# Sensor_Board.net
KiCad netlist of a schematic drawn in EAGLE
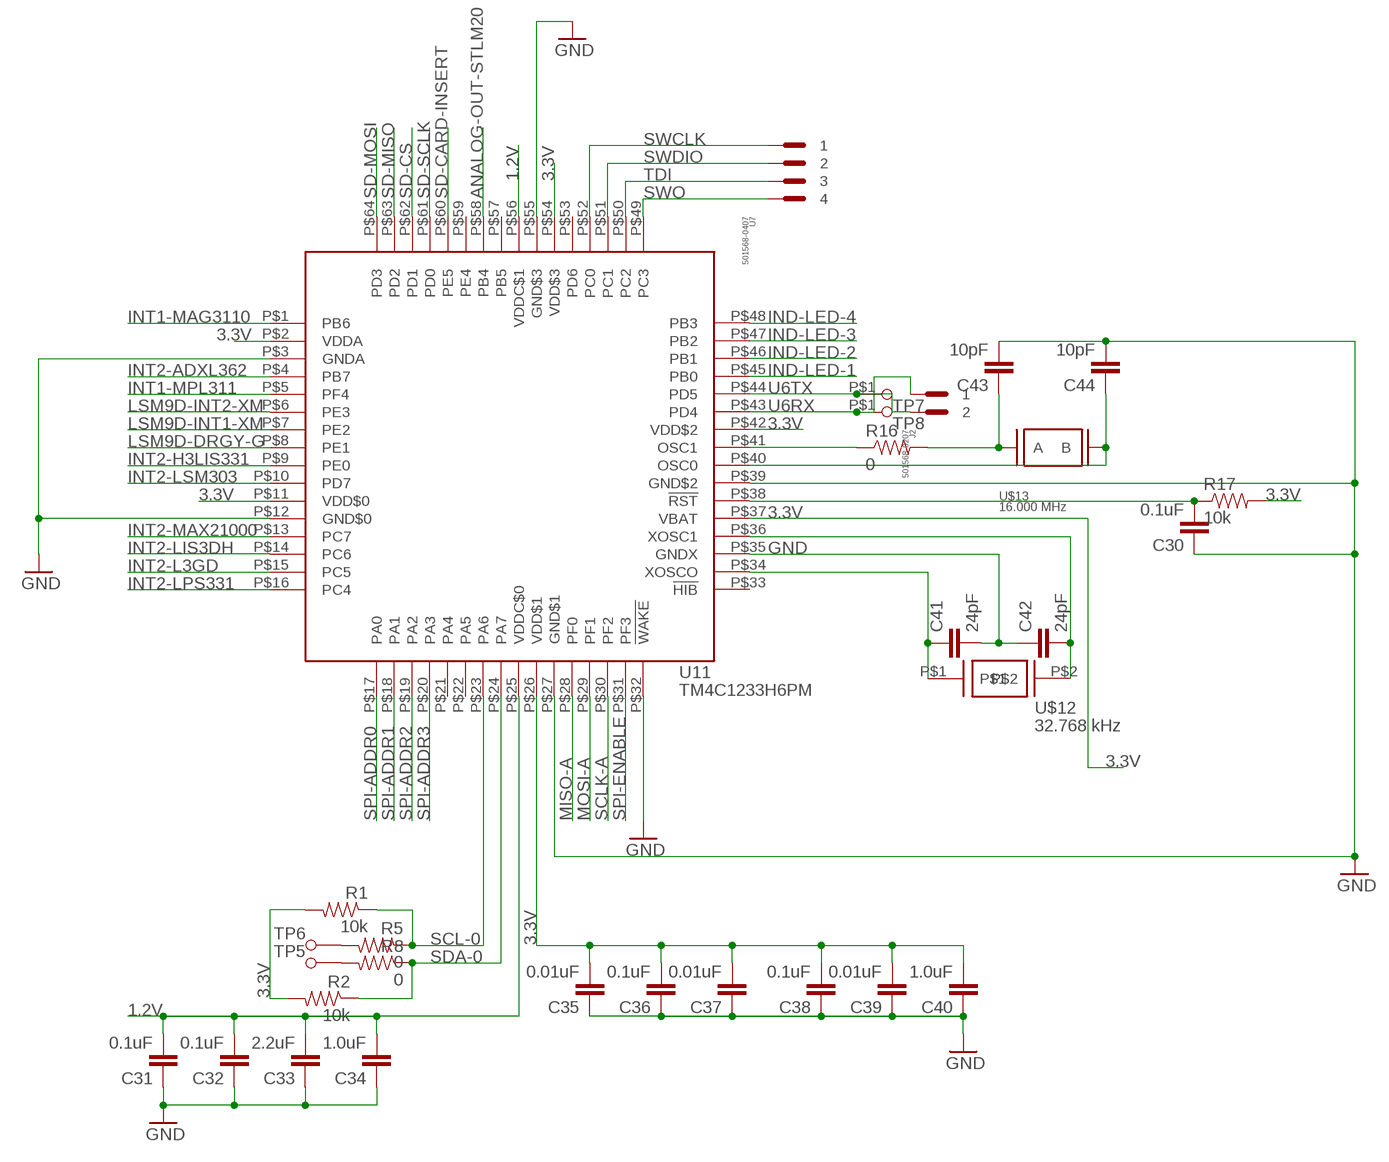
[diagram p0: schematic, sheet 1]
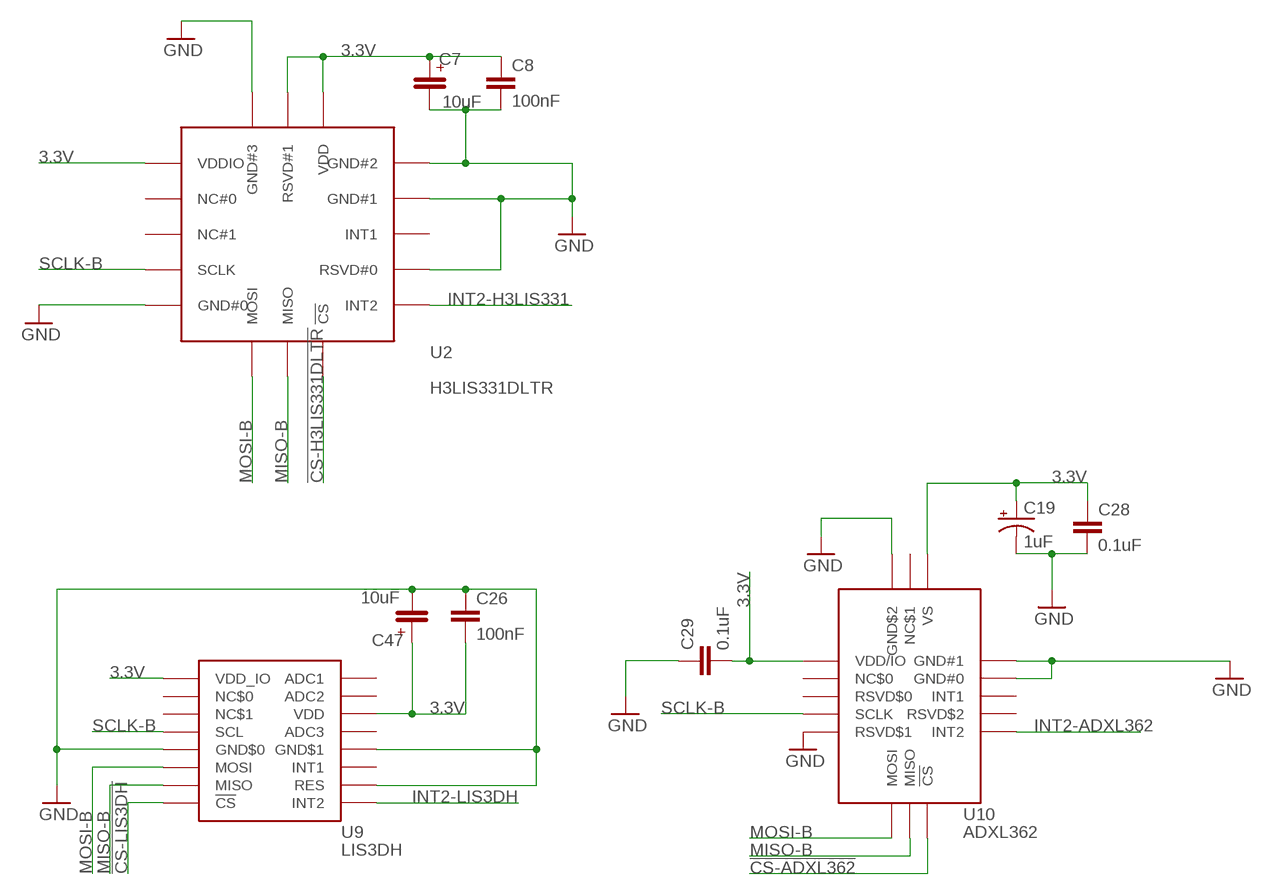
[diagram p1: schematic, sheet 2]
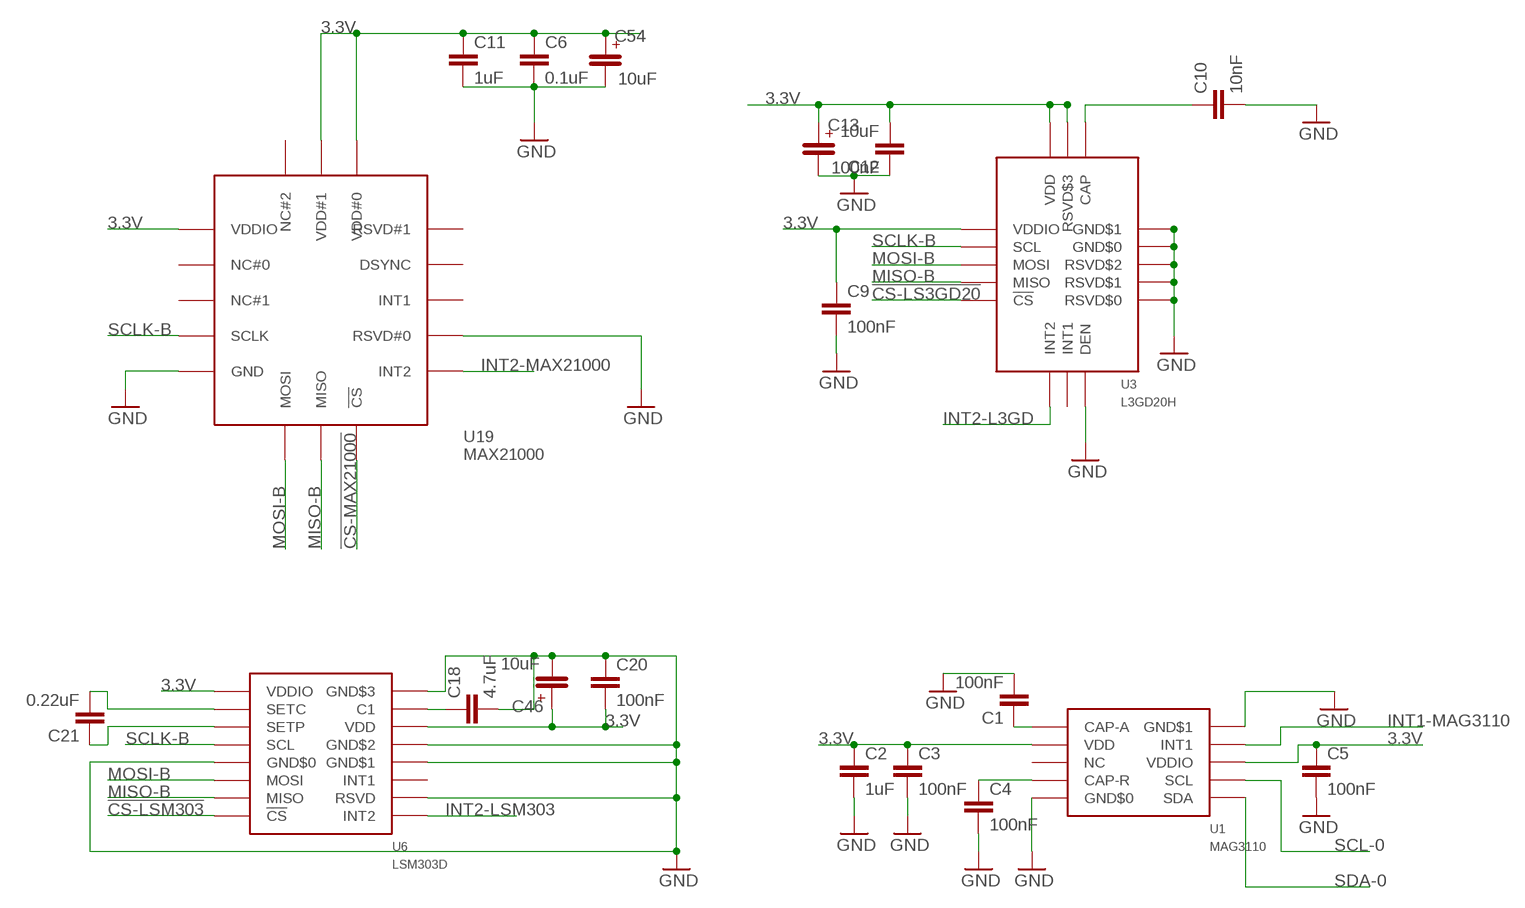
[diagram p2: schematic, sheet 3]
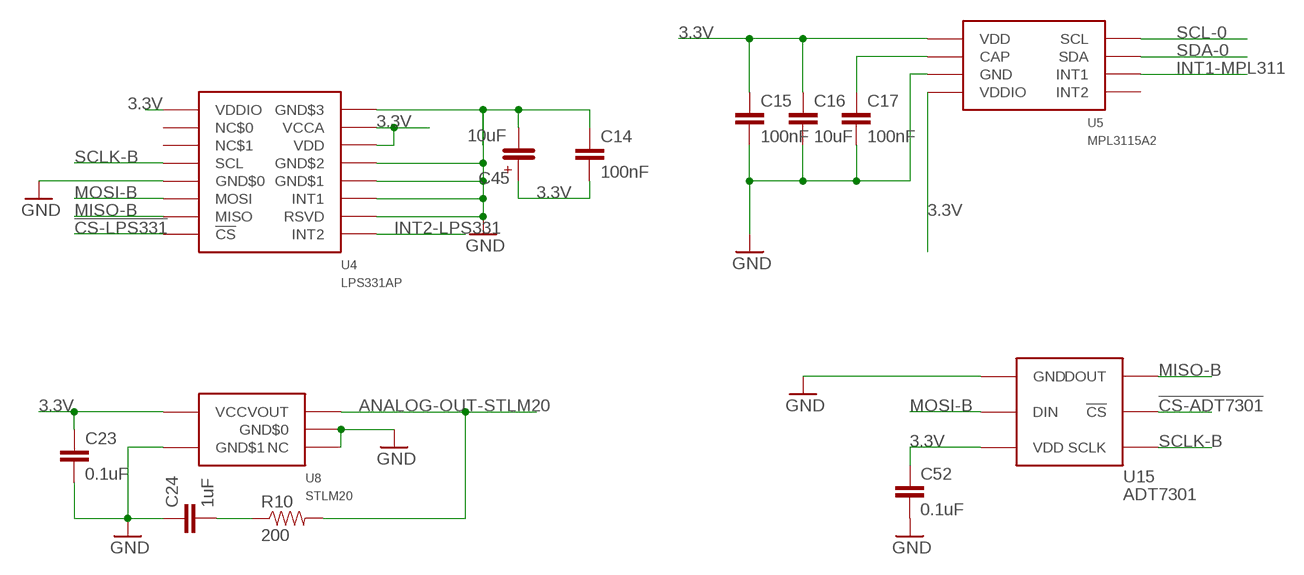
[diagram p3: schematic, sheet 4]
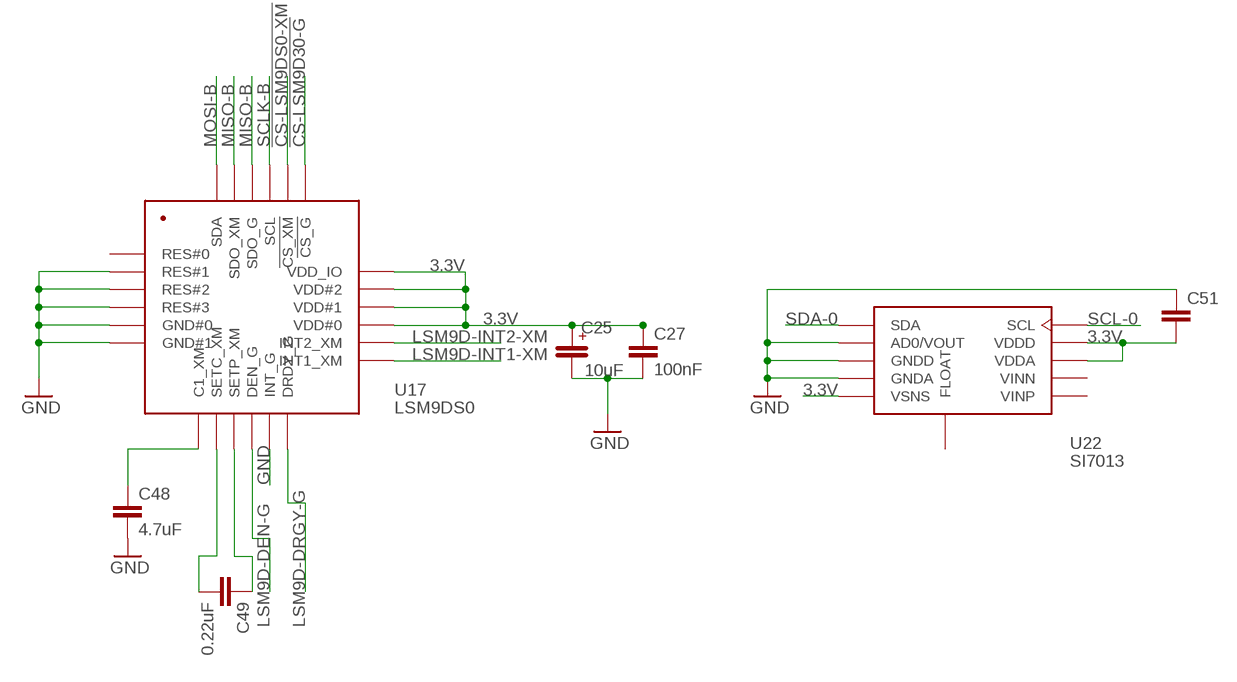
[diagram p4: schematic, sheet 5]
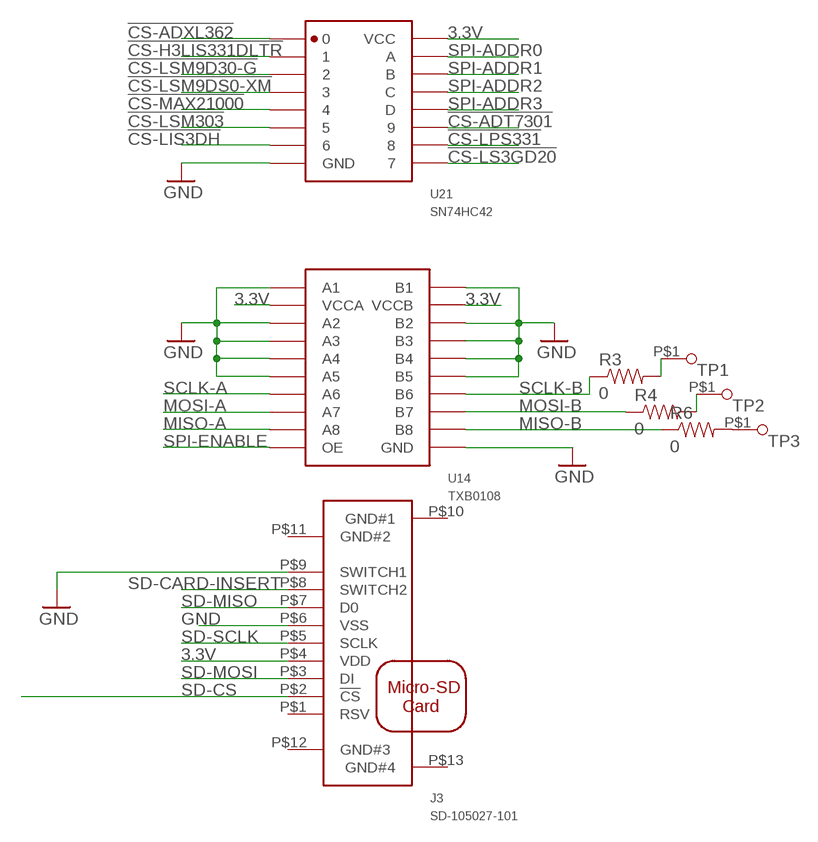
[diagram p5: schematic, sheet 6]
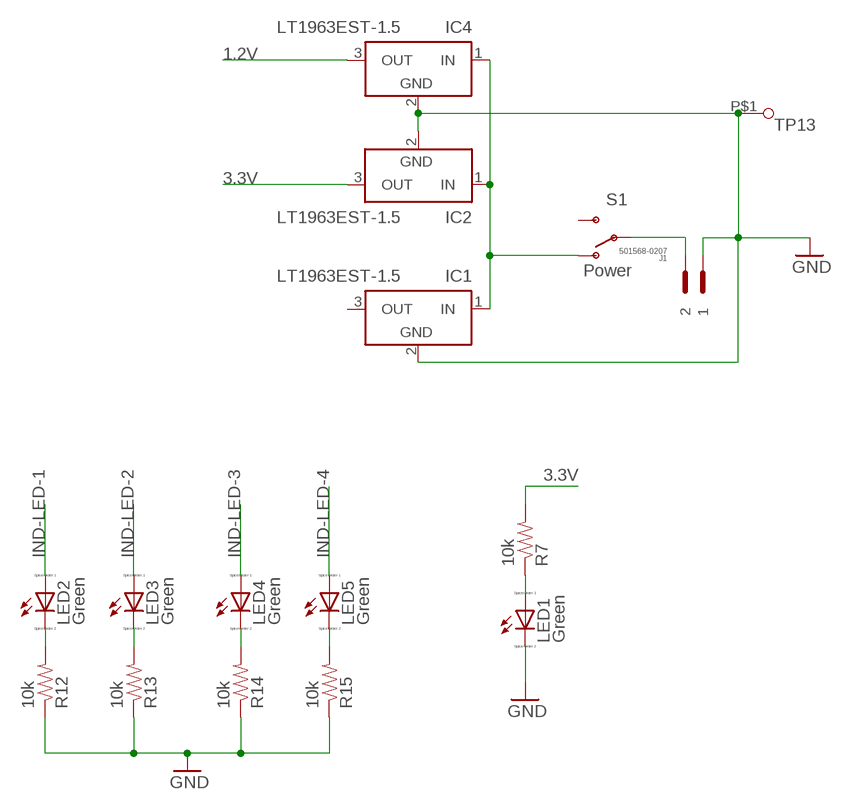
[diagram p6: schematic, sheet 7]

(export (version "E")
  (design (tool "Eeschema 10.0.6"))
  (components
    (comp (ref "C25")
      (value "10uF")
      (footprint "eagle-import:4.3X7.3SMD")
      (libsource (lib "eagle-import") (part "EEFCD0J100ER"))
    )
    (comp (ref "C27")
      (value "100nF")
      (footprint "eagle-import:C0402")
      (libsource (lib "eagle-import") (part "CAPACITOR0402"))
    )
    (comp (ref "C48")
      (value "4.7uF")
      (footprint "eagle-import:C0402")
      (libsource (lib "eagle-import") (part "CAPACITOR0402"))
    )
    (comp (ref "C49")
      (value "0.22uF")
      (footprint "eagle-import:C0402")
      (libsource (lib "eagle-import") (part "CAPACITOR0402"))
    )
    (comp (ref "C51")
      (value "CAPACITOR0402")
      (footprint "eagle-import:C0402")
      (libsource (lib "eagle-import") (part "CAPACITOR0402"))
    )
    (comp (ref "U17")
      (value "LSM9DS0")
      (footprint "eagle-import:LGA-24(4X4)")
      (libsource (lib "eagle-import") (part "LSM9DS0"))
    )
    (comp (ref "U22")
      (value "SI7013")
      (footprint "eagle-import:DFN-10(3X3)")
      (libsource (lib "eagle-import") (part "SI7013"))
    )
    (comp (ref "IC1")
      (value "LT1963EST-1.5")
      (footprint "eagle-import:SOT223")
      (libsource (lib "eagle-import") (part "LT1963EST-1.5"))
    )
    (comp (ref "IC2")
      (value "LT1963EST-1.5")
      (footprint "eagle-import:SOT223")
      (libsource (lib "eagle-import") (part "LT1963EST-1.5"))
    )
    (comp (ref "IC4")
      (value "LT1963EST-1.5")
      (footprint "eagle-import:SOT223")
      (libsource (lib "eagle-import") (part "LT1963EST-1.5"))
    )
    (comp (ref "J1")
      (value "501568-0207")
      (footprint "eagle-import:501568-0207")
      (libsource (lib "eagle-import") (part "501568-0207"))
    )
    (comp (ref "LED1")
      (value "Green")
      (footprint "eagle-import:LED_SML0603")
      (libsource (lib "eagle-import") (part "LED_ESML0603"))
    )
    (comp (ref "LED2")
      (value "Green")
      (footprint "eagle-import:LED_SML0603")
      (libsource (lib "eagle-import") (part "LED_ESML0603"))
    )
    (comp (ref "LED3")
      (value "Green")
      (footprint "eagle-import:LED_SML0603")
      (libsource (lib "eagle-import") (part "LED_ESML0603"))
    )
    (comp (ref "LED4")
      (value "Green")
      (footprint "eagle-import:LED_SML0603")
      (libsource (lib "eagle-import") (part "LED_ESML0603"))
    )
    (comp (ref "LED5")
      (value "Green")
      (footprint "eagle-import:LED_SML0603")
      (libsource (lib "eagle-import") (part "LED_ESML0603"))
    )
    (comp (ref "R7")
      (value "10k")
      (footprint "eagle-import:R0402")
      (libsource (lib "eagle-import") (part "RESISTOR"))
    )
    (comp (ref "R12")
      (value "10k")
      (footprint "eagle-import:R0402")
      (libsource (lib "eagle-import") (part "RESISTOR"))
    )
    (comp (ref "R13")
      (value "10k")
      (footprint "eagle-import:R0402")
      (libsource (lib "eagle-import") (part "RESISTOR"))
    )
    (comp (ref "R14")
      (value "10k")
      (footprint "eagle-import:R0402")
      (libsource (lib "eagle-import") (part "RESISTOR"))
    )
    (comp (ref "R15")
      (value "10k")
      (footprint "eagle-import:R0402")
      (libsource (lib "eagle-import") (part "RESISTOR"))
    )
    (comp (ref "S1")
      (value "Power")
      (footprint "eagle-import:SWITCH-SPST-SMD-A")
      (libsource (lib "eagle-import") (part "SWITCH-SPDT-SMD-A"))
    )
    (comp (ref "TP13")
      (value "TESTPAD(ROUND)")
      (footprint "eagle-import:TESTPAD(ROUND)")
      (libsource (lib "eagle-import") (part "Kas-Passives_TESTPAD(ROUND)"))
    )
    (comp (ref "C30")
      (value "0.1uF")
      (footprint "eagle-import:C0402")
      (libsource (lib "eagle-import") (part "CAPACITOR0402"))
    )
    (comp (ref "C31")
      (value "0.1uF")
      (footprint "eagle-import:C0402")
      (libsource (lib "eagle-import") (part "CAPACITOR0402"))
    )
    (comp (ref "C32")
      (value "0.1uF")
      (footprint "eagle-import:C0402")
      (libsource (lib "eagle-import") (part "CAPACITOR0402"))
    )
    (comp (ref "C33")
      (value "2.2uF")
      (footprint "eagle-import:C0402")
      (libsource (lib "eagle-import") (part "CAPACITOR0402"))
    )
    (comp (ref "C34")
      (value "1.0uF")
      (footprint "eagle-import:C0402")
      (libsource (lib "eagle-import") (part "CAPACITOR0402"))
    )
    (comp (ref "C35")
      (value "0.01uF")
      (footprint "eagle-import:C0402")
      (libsource (lib "eagle-import") (part "CAPACITOR0402"))
    )
    (comp (ref "C36")
      (value "0.1uF")
      (footprint "eagle-import:C0402")
      (libsource (lib "eagle-import") (part "CAPACITOR0402"))
    )
    (comp (ref "C37")
      (value "0.01uF")
      (footprint "eagle-import:C0402")
      (libsource (lib "eagle-import") (part "CAPACITOR0402"))
    )
    (comp (ref "C38")
      (value "0.1uF")
      (footprint "eagle-import:C0402")
      (libsource (lib "eagle-import") (part "CAPACITOR0402"))
    )
    (comp (ref "C39")
      (value "0.01uF")
      (footprint "eagle-import:C0402")
      (libsource (lib "eagle-import") (part "CAPACITOR0402"))
    )
    (comp (ref "C40")
      (value "1.0uF")
      (footprint "eagle-import:C0402")
      (libsource (lib "eagle-import") (part "CAPACITOR0402"))
    )
    (comp (ref "C41")
      (value "24pF")
      (footprint "eagle-import:C0402")
      (libsource (lib "eagle-import") (part "CAPACITOR0402"))
    )
    (comp (ref "C42")
      (value "24pF")
      (footprint "eagle-import:C0402")
      (libsource (lib "eagle-import") (part "CAPACITOR0402"))
    )
    (comp (ref "C43")
      (value "10pF")
      (footprint "eagle-import:C0402")
      (libsource (lib "eagle-import") (part "CAPACITOR0402"))
    )
    (comp (ref "C44")
      (value "10pF")
      (footprint "eagle-import:C0402")
      (libsource (lib "eagle-import") (part "CAPACITOR0402"))
    )
    (comp (ref "J2")
      (value "501568-0207")
      (footprint "eagle-import:501568-0207")
      (libsource (lib "eagle-import") (part "501568-0207"))
    )
    (comp (ref "R1")
      (value "10k")
      (footprint "eagle-import:R0402")
      (libsource (lib "eagle-import") (part "RESISTOR"))
    )
    (comp (ref "R2")
      (value "10k")
      (footprint "eagle-import:R0402")
      (libsource (lib "eagle-import") (part "RESISTOR"))
    )
    (comp (ref "R5")
      (value "0")
      (footprint "eagle-import:R0402")
      (libsource (lib "eagle-import") (part "RESISTOR"))
    )
    (comp (ref "R8")
      (value "0")
      (footprint "eagle-import:R0402")
      (libsource (lib "eagle-import") (part "RESISTOR"))
    )
    (comp (ref "R16")
      (value "0")
      (footprint "eagle-import:R0402")
      (libsource (lib "eagle-import") (part "RESISTOR"))
    )
    (comp (ref "R17")
      (value "10k")
      (footprint "eagle-import:R0402")
      (libsource (lib "eagle-import") (part "RESISTOR"))
    )
    (comp (ref "TP5")
      (value "TESTPAD(ROUND)")
      (footprint "eagle-import:TESTPAD(ROUND)")
      (libsource (lib "eagle-import") (part "TESTPAD(ROUND)"))
    )
    (comp (ref "TP6")
      (value "TESTPAD(ROUND)")
      (footprint "eagle-import:TESTPAD(ROUND)")
      (libsource (lib "eagle-import") (part "TESTPAD(ROUND)"))
    )
    (comp (ref "TP7")
      (value "TESTPAD(ROUND)")
      (footprint "eagle-import:TESTPAD(ROUND)")
      (libsource (lib "eagle-import") (part "Kas-Passives_TESTPAD(ROUND)"))
    )
    (comp (ref "TP8")
      (value "TESTPAD(ROUND)")
      (footprint "eagle-import:TESTPAD(ROUND)")
      (libsource (lib "eagle-import") (part "Kas-Passives_TESTPAD(ROUND)"))
    )
    (comp (ref "U$12")
      (value "32.768 kHz")
      (footprint "eagle-import:2-SMD(3.2X1.5)")
      (libsource (lib "eagle-import") (part "ABS07L"))
    )
    (comp (ref "U$13")
      (value "16.000 MHz")
      (footprint "eagle-import:4-SMD(3.2X2.5)")
      (libsource (lib "eagle-import") (part "NX3225GA"))
    )
    (comp (ref "U7")
      (value "501568-0407")
      (footprint "eagle-import:501568-0407")
      (libsource (lib "eagle-import") (part "501568-0407"))
    )
    (comp (ref "U11")
      (value "TM4C1233H6PM")
      (footprint "eagle-import:S-PQFP-G64")
      (libsource (lib "eagle-import") (part "TM4C1233H6PM"))
    )
    (comp (ref "C1")
      (value "100nF")
      (footprint "eagle-import:C0402")
      (libsource (lib "eagle-import") (part "CAPACITOR0402"))
    )
    (comp (ref "C2")
      (value "1uF")
      (footprint "eagle-import:C0402")
      (libsource (lib "eagle-import") (part "CAPACITOR0402"))
    )
    (comp (ref "C3")
      (value "100nF")
      (footprint "eagle-import:C0402")
      (libsource (lib "eagle-import") (part "CAPACITOR0402"))
    )
    (comp (ref "C4")
      (value "100nF")
      (footprint "eagle-import:C0402")
      (libsource (lib "eagle-import") (part "CAPACITOR0402"))
    )
    (comp (ref "C5")
      (value "100nF")
      (footprint "eagle-import:C0402")
      (libsource (lib "eagle-import") (part "CAPACITOR0402"))
    )
    (comp (ref "C6")
      (value "0.1uF")
      (footprint "eagle-import:C0402")
      (libsource (lib "eagle-import") (part "CAPACITOR0402"))
    )
    (comp (ref "C9")
      (value "100nF")
      (footprint "eagle-import:C0402")
      (libsource (lib "eagle-import") (part "CAPACITOR0402"))
    )
    (comp (ref "C10")
      (value "10nF")
      (footprint "eagle-import:C0402")
      (libsource (lib "eagle-import") (part "CAPACITOR0402"))
    )
    (comp (ref "C11")
      (value "1uF")
      (footprint "eagle-import:C0402")
      (libsource (lib "eagle-import") (part "CAPACITOR0402"))
    )
    (comp (ref "C12")
      (value "10uF")
      (footprint "eagle-import:C0402")
      (libsource (lib "eagle-import") (part "CAPACITOR0402"))
    )
    (comp (ref "C13")
      (value "100nF")
      (footprint "eagle-import:4.3X7.3SMD")
      (libsource (lib "eagle-import") (part "EEFCD0J100ER"))
    )
    (comp (ref "C18")
      (value "4.7uF")
      (footprint "eagle-import:C0402")
      (libsource (lib "eagle-import") (part "CAPACITOR0402"))
    )
    (comp (ref "C20")
      (value "100nF")
      (footprint "eagle-import:C0402")
      (libsource (lib "eagle-import") (part "CAPACITOR0402"))
    )
    (comp (ref "C21")
      (value "0.22uF")
      (footprint "eagle-import:C0402")
      (libsource (lib "eagle-import") (part "CAPACITOR0402"))
    )
    (comp (ref "C46")
      (value "10uF")
      (footprint "eagle-import:4.3X7.3SMD")
      (libsource (lib "eagle-import") (part "EEFCD0J100ER"))
    )
    (comp (ref "C54")
      (value "10uF")
      (footprint "eagle-import:4.3X7.3SMD")
      (libsource (lib "eagle-import") (part "EEFCD0J100ER"))
    )
    (comp (ref "U1")
      (value "MAG3110")
      (footprint "eagle-import:DFN-10(2X2)")
      (libsource (lib "eagle-import") (part "MAG3110"))
    )
    (comp (ref "U3")
      (value "L3GD20H")
      (footprint "eagle-import:LGA-16(3X3)")
      (libsource (lib "eagle-import") (part "L3GD20H"))
    )
    (comp (ref "U6")
      (value "LSM303D")
      (footprint "eagle-import:LGA-16(3X3)")
      (libsource (lib "eagle-import") (part "LSM303D"))
    )
    (comp (ref "U19")
      (value "MAX21000")
      (footprint "eagle-import:LGA-16(3X3)")
      (libsource (lib "eagle-import") (part "MAX21000"))
    )
    (comp (ref "J3")
      (value "SD-105027-101")
      (footprint "eagle-import:SD-105027-1001")
      (libsource (lib "eagle-import") (part "SD-105027-101"))
    )
    (comp (ref "R3")
      (value "0")
      (footprint "eagle-import:R0402")
      (libsource (lib "eagle-import") (part "RESISTOR"))
    )
    (comp (ref "R4")
      (value "0")
      (footprint "eagle-import:R0402")
      (libsource (lib "eagle-import") (part "RESISTOR"))
    )
    (comp (ref "R6")
      (value "0")
      (footprint "eagle-import:R0402")
      (libsource (lib "eagle-import") (part "RESISTOR"))
    )
    (comp (ref "TP1")
      (value "TESTPAD(ROUND)")
      (footprint "eagle-import:TESTPAD(ROUND)")
      (libsource (lib "eagle-import") (part "Kas-Passives_TESTPAD(ROUND)"))
    )
    (comp (ref "TP2")
      (value "TESTPAD(ROUND)")
      (footprint "eagle-import:TESTPAD(ROUND)")
      (libsource (lib "eagle-import") (part "Kas-Passives_TESTPAD(ROUND)"))
    )
    (comp (ref "TP3")
      (value "TESTPAD(ROUND)")
      (footprint "eagle-import:TESTPAD(ROUND)")
      (libsource (lib "eagle-import") (part "Kas-Passives_TESTPAD(ROUND)"))
    )
    (comp (ref "U14")
      (value "TXB0108")
      (footprint "eagle-import:TSSOP-(PW)-20")
      (libsource (lib "eagle-import") (part "TXB0108"))
    )
    (comp (ref "U21")
      (value "SN74HC42")
      (footprint "eagle-import:SOIC-16")
      (libsource (lib "eagle-import") (part "SN74HC42"))
    )
    (comp (ref "C14")
      (value "100nF")
      (footprint "eagle-import:C0402")
      (libsource (lib "eagle-import") (part "CAPACITOR0402"))
    )
    (comp (ref "C15")
      (value "100nF")
      (footprint "eagle-import:C0402")
      (libsource (lib "eagle-import") (part "CAPACITOR0402"))
    )
    (comp (ref "C16")
      (value "10uF")
      (footprint "eagle-import:C0402")
      (libsource (lib "eagle-import") (part "CAPACITOR0402"))
    )
    (comp (ref "C17")
      (value "100nF")
      (footprint "eagle-import:C0402")
      (libsource (lib "eagle-import") (part "CAPACITOR0402"))
    )
    (comp (ref "C23")
      (value "0.1uF")
      (footprint "eagle-import:C0402")
      (libsource (lib "eagle-import") (part "CAPACITOR0402"))
    )
    (comp (ref "C24")
      (value "1uF")
      (footprint "eagle-import:C0402")
      (libsource (lib "eagle-import") (part "CAPACITOR0402"))
    )
    (comp (ref "C45")
      (value "10uF")
      (footprint "eagle-import:4.3X7.3SMD")
      (libsource (lib "eagle-import") (part "EEFCD0J100ER"))
    )
    (comp (ref "C52")
      (value "0.1uF")
      (footprint "eagle-import:C0402")
      (libsource (lib "eagle-import") (part "CAPACITOR0402"))
    )
    (comp (ref "R10")
      (value "200")
      (footprint "eagle-import:R0402")
      (libsource (lib "eagle-import") (part "RESISTOR"))
    )
    (comp (ref "U4")
      (value "LPS331AP")
      (footprint "eagle-import:LGA-16(3X3)")
      (libsource (lib "eagle-import") (part "LPS331AP"))
    )
    (comp (ref "U5")
      (value "MPL3115A2")
      (footprint "eagle-import:LGA-8(5X3)")
      (libsource (lib "eagle-import") (part "MPL3115A2"))
    )
    (comp (ref "U8")
      (value "STLM20")
      (footprint "eagle-import:SOT323-5L")
      (libsource (lib "eagle-import") (part "STLM20"))
    )
    (comp (ref "U15")
      (value "ADT7301")
      (footprint "eagle-import:SOT23-6")
      (libsource (lib "eagle-import") (part "ADT7301"))
    )
    (comp (ref "C7")
      (value "10uF")
      (footprint "eagle-import:4.3X7.3SMD")
      (libsource (lib "eagle-import") (part "EEFCD0J100ER"))
    )
    (comp (ref "C8")
      (value "100nF")
      (footprint "eagle-import:C0402")
      (libsource (lib "eagle-import") (part "CAPACITOR0402"))
    )
    (comp (ref "C19")
      (value "1uF")
      (footprint "eagle-import:EIA6032")
      (libsource (lib "eagle-import") (part "CAP_POL6032"))
    )
    (comp (ref "C26")
      (value "100nF")
      (footprint "eagle-import:C0402")
      (libsource (lib "eagle-import") (part "CAPACITOR0402"))
    )
    (comp (ref "C28")
      (value "0.1uF")
      (footprint "eagle-import:C0402")
      (libsource (lib "eagle-import") (part "CAPACITOR0402"))
    )
    (comp (ref "C29")
      (value "0.1uF")
      (footprint "eagle-import:C0402")
      (libsource (lib "eagle-import") (part "CAPACITOR0402"))
    )
    (comp (ref "C47")
      (value "10uF")
      (footprint "eagle-import:4.3X7.3SMD")
      (libsource (lib "eagle-import") (part "EEFCD0J100ER"))
    )
    (comp (ref "U2")
      (value "H3LIS331DLTR")
      (footprint "eagle-import:LGA-16(3X3)")
      (libsource (lib "eagle-import") (part "H3LIS331DLTR"))
    )
    (comp (ref "U9")
      (value "LIS3DH")
      (footprint "eagle-import:LGA-16(3X3)")
      (libsource (lib "eagle-import") (part "LIS3DH"))
    )
    (comp (ref "U10")
      (value "ADXL362")
      (footprint "eagle-import:LGA-16(3X3.25)")
      (libsource (lib "eagle-import") (part "ADXL362"))
    )
  )
  (nets
    (net (code "1") (name "1.2V") (class "Default")
      (node (ref "C31") (pin "2") (pinfunction "2_2") (pintype "passive"))
      (node (ref "C32") (pin "2") (pinfunction "2_2") (pintype "passive"))
      (node (ref "C33") (pin "2") (pinfunction "2_2") (pintype "passive"))
      (node (ref "C34") (pin "2") (pinfunction "2_2") (pintype "passive"))
      (node (ref "IC4") (pin "3") (pinfunction "OUT_3") (pintype "output"))
      (node (ref "U11") (pin "P$25") (pinfunction "VDDC$0_P$25") (pintype "bidirectional"))
      (node (ref "U11") (pin "P$56") (pinfunction "VDDC$1_P$56") (pintype "bidirectional"))
    )
    (net (code "2") (name "3.3V") (class "Default")
      (node (ref "C11") (pin "1") (pinfunction "1_1") (pintype "passive"))
      (node (ref "C12") (pin "2") (pinfunction "2_2") (pintype "passive"))
      (node (ref "C13") (pin "P$1") (pintype "bidirectional"))
      (node (ref "C14") (pin "2") (pinfunction "2_2") (pintype "passive"))
      (node (ref "C15") (pin "1") (pinfunction "1_1") (pintype "passive"))
      (node (ref "C16") (pin "1") (pinfunction "1_1") (pintype "passive"))
      (node (ref "C19") (pin "P$1") (pinfunction "+_P$1") (pintype "passive"))
      (node (ref "C2") (pin "1") (pinfunction "1_1") (pintype "passive"))
      (node (ref "C20") (pin "2") (pinfunction "2_2") (pintype "passive"))
      (node (ref "C23") (pin "1") (pinfunction "1_1") (pintype "passive"))
      (node (ref "C25") (pin "P$1") (pintype "bidirectional"))
      (node (ref "C26") (pin "2") (pinfunction "2_2") (pintype "passive"))
      (node (ref "C27") (pin "1") (pinfunction "1_1") (pintype "passive"))
      (node (ref "C28") (pin "1") (pinfunction "1_1") (pintype "passive"))
      (node (ref "C29") (pin "2") (pinfunction "2_2") (pintype "passive"))
      (node (ref "C3") (pin "1") (pinfunction "1_1") (pintype "passive"))
      (node (ref "C35") (pin "2") (pinfunction "2_2") (pintype "passive"))
      (node (ref "C36") (pin "2") (pinfunction "2_2") (pintype "passive"))
      (node (ref "C37") (pin "2") (pinfunction "2_2") (pintype "passive"))
      (node (ref "C38") (pin "2") (pinfunction "2_2") (pintype "passive"))
      (node (ref "C39") (pin "2") (pinfunction "2_2") (pintype "passive"))
      (node (ref "C40") (pin "2") (pinfunction "2_2") (pintype "passive"))
      (node (ref "C45") (pin "P$1") (pintype "bidirectional"))
      (node (ref "C46") (pin "P$1") (pintype "bidirectional"))
      (node (ref "C47") (pin "P$1") (pintype "bidirectional"))
      (node (ref "C5") (pin "1") (pinfunction "1_1") (pintype "passive"))
      (node (ref "C51") (pin "2") (pinfunction "2_2") (pintype "passive"))
      (node (ref "C52") (pin "1") (pinfunction "1_1") (pintype "passive"))
      (node (ref "C54") (pin "P$1") (pintype "bidirectional"))
      (node (ref "C6") (pin "1") (pinfunction "1_1") (pintype "passive"))
      (node (ref "C7") (pin "P$1") (pintype "bidirectional"))
      (node (ref "C8") (pin "1") (pinfunction "1_1") (pintype "passive"))
      (node (ref "C9") (pin "1") (pinfunction "1_1") (pintype "passive"))
      (node (ref "IC2") (pin "3") (pinfunction "OUT_3") (pintype "output"))
      (node (ref "J3") (pin "P$4") (pinfunction "VDD_P$4") (pintype "bidirectional"))
      (node (ref "R1") (pin "2") (pinfunction "2_2") (pintype "passive"))
      (node (ref "R17") (pin "2") (pinfunction "2_2") (pintype "passive"))
      (node (ref "R2") (pin "2") (pinfunction "2_2") (pintype "passive"))
      (node (ref "R7") (pin "2") (pinfunction "2_2") (pintype "passive"))
      (node (ref "U1") (pin "P$2") (pinfunction "VDD_P$2") (pintype "bidirectional"))
      (node (ref "U1") (pin "P$8") (pinfunction "VDDIO_P$8") (pintype "bidirectional"))
      (node (ref "U10") (pin "P$1") (pinfunction "VDD/IO_P$1") (pintype "bidirectional"))
      (node (ref "U10") (pin "P$14") (pinfunction "VS_P$14") (pintype "bidirectional"))
      (node (ref "U11") (pin "P$11") (pinfunction "VDD$0_P$11") (pintype "bidirectional"))
      (node (ref "U11") (pin "P$2") (pinfunction "VDDA_P$2") (pintype "bidirectional"))
      (node (ref "U11") (pin "P$26") (pinfunction "VDD$1_P$26") (pintype "bidirectional"))
      (node (ref "U11") (pin "P$37") (pinfunction "VBAT_P$37") (pintype "bidirectional"))
      (node (ref "U11") (pin "P$42") (pinfunction "VDD$2_P$42") (pintype "bidirectional"))
      (node (ref "U11") (pin "P$54") (pinfunction "VDD$3_P$54") (pintype "bidirectional"))
      (node (ref "U14") (pin "P$19") (pinfunction "VCCB_P$19") (pintype "bidirectional"))
      (node (ref "U14") (pin "P$2") (pinfunction "VCCA_P$2") (pintype "bidirectional"))
      (node (ref "U15") (pin "P$3") (pinfunction "VDD_P$3") (pintype "bidirectional"))
      (node (ref "U17") (pin "P$15") (pinfunction "VDD#0_P$15") (pintype "bidirectional"))
      (node (ref "U17") (pin "P$16") (pinfunction "VDD#1_P$16") (pintype "bidirectional"))
      (node (ref "U17") (pin "P$17") (pinfunction "VDD#2_P$17") (pintype "bidirectional"))
      (node (ref "U17") (pin "P$18") (pinfunction "VDD_IO_P$18") (pintype "bidirectional"))
      (node (ref "U19") (pin "P$1") (pinfunction "VDDIO_P$1") (pintype "bidirectional"))
      (node (ref "U19") (pin "P$14") (pinfunction "VDD#0_P$14") (pintype "bidirectional"))
      (node (ref "U19") (pin "P$15") (pinfunction "VDD#1_P$15") (pintype "bidirectional"))
      (node (ref "U2") (pin "P$1") (pinfunction "VDDIO_P$1") (pintype "bidirectional"))
      (node (ref "U2") (pin "P$14") (pinfunction "VDD_P$14") (pintype "bidirectional"))
      (node (ref "U2") (pin "P$15") (pinfunction "RSVD#1_P$15") (pintype "bidirectional"))
      (node (ref "U21") (pin "P$16") (pinfunction "VCC_P$16") (pintype "bidirectional"))
      (node (ref "U22") (pin "P$5") (pinfunction "VSNS_P$5") (pintype "bidirectional"))
      (node (ref "U22") (pin "P$8") (pinfunction "VDDA_P$8") (pintype "bidirectional"))
      (node (ref "U22") (pin "P$9") (pinfunction "VDDD_P$9") (pintype "bidirectional"))
      (node (ref "U3") (pin "P$1") (pinfunction "VDDIO_P$1") (pintype "bidirectional"))
      (node (ref "U3") (pin "P$15") (pinfunction "RSVD$3_P$15") (pintype "bidirectional"))
      (node (ref "U3") (pin "P$16") (pinfunction "VDD_P$16") (pintype "bidirectional"))
      (node (ref "U4") (pin "P$1") (pinfunction "VDDIO_P$1") (pintype "bidirectional"))
      (node (ref "U4") (pin "P$14") (pinfunction "VDD_P$14") (pintype "bidirectional"))
      (node (ref "U4") (pin "P$15") (pinfunction "VCCA_P$15") (pintype "bidirectional"))
      (node (ref "U5") (pin "P$1") (pinfunction "VDD_P$1") (pintype "bidirectional"))
      (node (ref "U5") (pin "P$4") (pinfunction "VDDIO_P$4") (pintype "bidirectional"))
      (node (ref "U6") (pin "P$1") (pinfunction "VDDIO_P$1") (pintype "bidirectional"))
      (node (ref "U6") (pin "P$14") (pinfunction "VDD_P$14") (pintype "bidirectional"))
      (node (ref "U8") (pin "P$4") (pinfunction "VCC_P$4") (pintype "bidirectional"))
      (node (ref "U9") (pin "P$1") (pinfunction "VDD_IO_P$1") (pintype "bidirectional"))
      (node (ref "U9") (pin "P$14") (pinfunction "VDD_P$14") (pintype "bidirectional"))
    )
    (net (code "3") (name "ANALOG-OUT-STLM20") (class "Default")
      (node (ref "R10") (pin "2") (pinfunction "2_2") (pintype "passive"))
      (node (ref "U11") (pin "P$58") (pinfunction "PB4_P$58") (pintype "bidirectional"))
      (node (ref "U8") (pin "P$3") (pinfunction "VOUT_P$3") (pintype "bidirectional"))
    )
    (net (code "4") (name "GND") (class "Default")
      (node (ref "C1") (pin "2") (pinfunction "2_2") (pintype "passive"))
      (node (ref "C10") (pin "2") (pinfunction "2_2") (pintype "passive"))
      (node (ref "C11") (pin "2") (pinfunction "2_2") (pintype "passive"))
      (node (ref "C12") (pin "1") (pinfunction "1_1") (pintype "passive"))
      (node (ref "C13") (pin "P$2") (pintype "bidirectional"))
      (node (ref "C14") (pin "1") (pinfunction "1_1") (pintype "passive"))
      (node (ref "C15") (pin "2") (pinfunction "2_2") (pintype "passive"))
      (node (ref "C16") (pin "2") (pinfunction "2_2") (pintype "passive"))
      (node (ref "C17") (pin "2") (pinfunction "2_2") (pintype "passive"))
      (node (ref "C18") (pin "2") (pinfunction "2_2") (pintype "passive"))
      (node (ref "C19") (pin "P$2") (pinfunction "-_P$2") (pintype "passive"))
      (node (ref "C2") (pin "2") (pinfunction "2_2") (pintype "passive"))
      (node (ref "C20") (pin "1") (pinfunction "1_1") (pintype "passive"))
      (node (ref "C23") (pin "2") (pinfunction "2_2") (pintype "passive"))
      (node (ref "C24") (pin "1") (pinfunction "1_1") (pintype "passive"))
      (node (ref "C25") (pin "P$2") (pintype "bidirectional"))
      (node (ref "C26") (pin "1") (pinfunction "1_1") (pintype "passive"))
      (node (ref "C27") (pin "2") (pinfunction "2_2") (pintype "passive"))
      (node (ref "C28") (pin "2") (pinfunction "2_2") (pintype "passive"))
      (node (ref "C29") (pin "1") (pinfunction "1_1") (pintype "passive"))
      (node (ref "C3") (pin "2") (pinfunction "2_2") (pintype "passive"))
      (node (ref "C30") (pin "1") (pinfunction "1_1") (pintype "passive"))
      (node (ref "C31") (pin "1") (pinfunction "1_1") (pintype "passive"))
      (node (ref "C32") (pin "1") (pinfunction "1_1") (pintype "passive"))
      (node (ref "C33") (pin "1") (pinfunction "1_1") (pintype "passive"))
      (node (ref "C34") (pin "1") (pinfunction "1_1") (pintype "passive"))
      (node (ref "C35") (pin "1") (pinfunction "1_1") (pintype "passive"))
      (node (ref "C36") (pin "1") (pinfunction "1_1") (pintype "passive"))
      (node (ref "C37") (pin "1") (pinfunction "1_1") (pintype "passive"))
      (node (ref "C38") (pin "1") (pinfunction "1_1") (pintype "passive"))
      (node (ref "C39") (pin "1") (pinfunction "1_1") (pintype "passive"))
      (node (ref "C4") (pin "2") (pinfunction "2_2") (pintype "passive"))
      (node (ref "C40") (pin "1") (pinfunction "1_1") (pintype "passive"))
      (node (ref "C41") (pin "2") (pinfunction "2_2") (pintype "passive"))
      (node (ref "C42") (pin "1") (pinfunction "1_1") (pintype "passive"))
      (node (ref "C43") (pin "2") (pinfunction "2_2") (pintype "passive"))
      (node (ref "C44") (pin "2") (pinfunction "2_2") (pintype "passive"))
      (node (ref "C45") (pin "P$2") (pintype "bidirectional"))
      (node (ref "C46") (pin "P$2") (pintype "bidirectional"))
      (node (ref "C47") (pin "P$2") (pintype "bidirectional"))
      (node (ref "C48") (pin "2") (pinfunction "2_2") (pintype "passive"))
      (node (ref "C5") (pin "2") (pinfunction "2_2") (pintype "passive"))
      (node (ref "C51") (pin "1") (pinfunction "1_1") (pintype "passive"))
      (node (ref "C52") (pin "2") (pinfunction "2_2") (pintype "passive"))
      (node (ref "C54") (pin "P$2") (pintype "bidirectional"))
      (node (ref "C6") (pin "2") (pinfunction "2_2") (pintype "passive"))
      (node (ref "C7") (pin "P$2") (pintype "bidirectional"))
      (node (ref "C8") (pin "2") (pinfunction "2_2") (pintype "passive"))
      (node (ref "C9") (pin "2") (pinfunction "2_2") (pintype "passive"))
      (node (ref "IC1") (pin "2") (pinfunction "GND_2") (pintype "power_in"))
      (node (ref "IC2") (pin "2") (pinfunction "GND_2") (pintype "power_in"))
      (node (ref "IC4") (pin "2") (pinfunction "GND_2") (pintype "power_in"))
      (node (ref "J1") (pin "P$1") (pinfunction "1_P$1") (pintype "bidirectional"))
      (node (ref "J3") (pin "P$6") (pinfunction "VSS_P$6") (pintype "bidirectional"))
      (node (ref "J3") (pin "P$9") (pinfunction "SWITCH1_P$9") (pintype "bidirectional"))
      (node (ref "LED1") (pin "C") (pinfunction "C_C") (pintype "passive"))
      (node (ref "R12") (pin "1") (pinfunction "1_1") (pintype "passive"))
      (node (ref "R13") (pin "1") (pinfunction "1_1") (pintype "passive"))
      (node (ref "R14") (pin "1") (pinfunction "1_1") (pintype "passive"))
      (node (ref "R15") (pin "1") (pinfunction "1_1") (pintype "passive"))
      (node (ref "TP13") (pin "P$1") (pinfunction "P$1_P$1") (pintype "bidirectional"))
      (node (ref "U1") (pin "P$10") (pinfunction "GND$1_P$10") (pintype "bidirectional"))
      (node (ref "U1") (pin "P$5") (pinfunction "GND$0_P$5") (pintype "bidirectional"))
      (node (ref "U10") (pin "P$12") (pinfunction "GND#0_P$12") (pintype "bidirectional"))
      (node (ref "U10") (pin "P$13") (pinfunction "GND#1_P$13") (pintype "bidirectional"))
      (node (ref "U10") (pin "P$16") (pinfunction "GND$2_P$16") (pintype "bidirectional"))
      (node (ref "U10") (pin "P$5") (pinfunction "RSVD$1_P$5") (pintype "bidirectional"))
      (node (ref "U11") (pin "P$12") (pinfunction "GND$0_P$12") (pintype "bidirectional"))
      (node (ref "U11") (pin "P$27") (pinfunction "GND$1_P$27") (pintype "bidirectional"))
      (node (ref "U11") (pin "P$3") (pinfunction "GNDA_P$3") (pintype "bidirectional"))
      (node (ref "U11") (pin "P$32") (pinfunction "~{WAKE}_P$32") (pintype "bidirectional"))
      (node (ref "U11") (pin "P$35") (pinfunction "GNDX_P$35") (pintype "bidirectional"))
      (node (ref "U11") (pin "P$39") (pinfunction "GND$2_P$39") (pintype "bidirectional"))
      (node (ref "U11") (pin "P$55") (pinfunction "GND$3_P$55") (pintype "bidirectional"))
      (node (ref "U14") (pin "P$1") (pinfunction "A1_P$1") (pintype "bidirectional"))
      (node (ref "U14") (pin "P$11") (pinfunction "GND_P$11") (pintype "bidirectional"))
      (node (ref "U14") (pin "P$15") (pinfunction "B5_P$15") (pintype "bidirectional"))
      (node (ref "U14") (pin "P$16") (pinfunction "B4_P$16") (pintype "bidirectional"))
      (node (ref "U14") (pin "P$17") (pinfunction "B3_P$17") (pintype "bidirectional"))
      (node (ref "U14") (pin "P$18") (pinfunction "B2_P$18") (pintype "bidirectional"))
      (node (ref "U14") (pin "P$20") (pinfunction "B1_P$20") (pintype "bidirectional"))
      (node (ref "U14") (pin "P$3") (pinfunction "A2_P$3") (pintype "bidirectional"))
      (node (ref "U14") (pin "P$4") (pinfunction "A3_P$4") (pintype "bidirectional"))
      (node (ref "U14") (pin "P$5") (pinfunction "A4_P$5") (pintype "bidirectional"))
      (node (ref "U14") (pin "P$6") (pinfunction "A5_P$6") (pintype "bidirectional"))
      (node (ref "U15") (pin "P$1") (pinfunction "GND_P$1") (pintype "bidirectional"))
      (node (ref "U17") (pin "P$11") (pinfunction "INT_G_P$11") (pintype "bidirectional"))
      (node (ref "U17") (pin "P$2") (pinfunction "RES#1_P$2") (pintype "bidirectional"))
      (node (ref "U17") (pin "P$3") (pinfunction "RES#2_P$3") (pintype "bidirectional"))
      (node (ref "U17") (pin "P$4") (pinfunction "RES#3_P$4") (pintype "bidirectional"))
      (node (ref "U17") (pin "P$5") (pinfunction "GND#0_P$5") (pintype "bidirectional"))
      (node (ref "U17") (pin "P$6") (pinfunction "GND#1_P$6") (pintype "bidirectional"))
      (node (ref "U19") (pin "P$10") (pinfunction "RSVD#0_P$10") (pintype "bidirectional"))
      (node (ref "U19") (pin "P$5") (pinfunction "GND_P$5") (pintype "bidirectional"))
      (node (ref "U2") (pin "P$10") (pinfunction "RSVD#0_P$10") (pintype "bidirectional"))
      (node (ref "U2") (pin "P$12") (pinfunction "GND#1_P$12") (pintype "bidirectional"))
      (node (ref "U2") (pin "P$13") (pinfunction "GND#2_P$13") (pintype "bidirectional"))
      (node (ref "U2") (pin "P$16") (pinfunction "GND#3_P$16") (pintype "bidirectional"))
      (node (ref "U2") (pin "P$5") (pinfunction "GND#0_P$5") (pintype "bidirectional"))
      (node (ref "U21") (pin "P$8") (pinfunction "GND_P$8") (pintype "bidirectional"))
      (node (ref "U22") (pin "P$2") (pinfunction "AD0/VOUT_P$2") (pintype "bidirectional"))
      (node (ref "U22") (pin "P$3") (pinfunction "GNDD_P$3") (pintype "bidirectional"))
      (node (ref "U22") (pin "P$4") (pinfunction "GNDA_P$4") (pintype "bidirectional"))
      (node (ref "U3") (pin "P$10") (pinfunction "RSVD$1_P$10") (pintype "bidirectional"))
      (node (ref "U3") (pin "P$11") (pinfunction "RSVD$2_P$11") (pintype "bidirectional"))
      (node (ref "U3") (pin "P$12") (pinfunction "GND$0_P$12") (pintype "bidirectional"))
      (node (ref "U3") (pin "P$13") (pinfunction "GND$1_P$13") (pintype "bidirectional"))
      (node (ref "U3") (pin "P$8") (pinfunction "DEN_P$8") (pintype "bidirectional"))
      (node (ref "U3") (pin "P$9") (pinfunction "RSVD$0_P$9") (pintype "bidirectional"))
      (node (ref "U4") (pin "P$10") (pinfunction "RSVD_P$10") (pintype "bidirectional"))
      (node (ref "U4") (pin "P$11") (pinfunction "INT1_P$11") (pintype "bidirectional"))
      (node (ref "U4") (pin "P$12") (pinfunction "GND$1_P$12") (pintype "bidirectional"))
      (node (ref "U4") (pin "P$13") (pinfunction "GND$2_P$13") (pintype "bidirectional"))
      (node (ref "U4") (pin "P$16") (pinfunction "GND$3_P$16") (pintype "bidirectional"))
      (node (ref "U4") (pin "P$5") (pinfunction "GND$0_P$5") (pintype "bidirectional"))
      (node (ref "U5") (pin "P$3") (pinfunction "GND_P$3") (pintype "bidirectional"))
      (node (ref "U6") (pin "P$10") (pinfunction "RSVD_P$10") (pintype "bidirectional"))
      (node (ref "U6") (pin "P$12") (pinfunction "GND$1_P$12") (pintype "bidirectional"))
      (node (ref "U6") (pin "P$13") (pinfunction "GND$2_P$13") (pintype "bidirectional"))
      (node (ref "U6") (pin "P$16") (pinfunction "GND$3_P$16") (pintype "bidirectional"))
      (node (ref "U6") (pin "P$5") (pinfunction "GND$0_P$5") (pintype "bidirectional"))
      (node (ref "U8") (pin "P$1") (pinfunction "NC_P$1") (pintype "bidirectional"))
      (node (ref "U8") (pin "P$2") (pinfunction "GND$0_P$2") (pintype "bidirectional"))
      (node (ref "U8") (pin "P$5") (pinfunction "GND$1_P$5") (pintype "bidirectional"))
      (node (ref "U9") (pin "P$10") (pinfunction "RES_P$10") (pintype "bidirectional"))
      (node (ref "U9") (pin "P$12") (pinfunction "GND$1_P$12") (pintype "bidirectional"))
      (node (ref "U9") (pin "P$5") (pinfunction "GND$0_P$5") (pintype "bidirectional"))
    )
    (net (code "5") (name "IND-LED-1") (class "Default")
      (node (ref "LED2") (pin "A") (pinfunction "A_A") (pintype "passive"))
      (node (ref "U11") (pin "P$45") (pinfunction "PB0_P$45") (pintype "bidirectional"))
    )
    (net (code "6") (name "IND-LED-2") (class "Default")
      (node (ref "LED3") (pin "A") (pinfunction "A_A") (pintype "passive"))
      (node (ref "U11") (pin "P$46") (pinfunction "PB1_P$46") (pintype "bidirectional"))
    )
    (net (code "7") (name "IND-LED-3") (class "Default")
      (node (ref "LED4") (pin "A") (pinfunction "A_A") (pintype "passive"))
      (node (ref "U11") (pin "P$47") (pinfunction "PB2_P$47") (pintype "bidirectional"))
    )
    (net (code "8") (name "IND-LED-4") (class "Default")
      (node (ref "LED5") (pin "A") (pinfunction "A_A") (pintype "passive"))
      (node (ref "U11") (pin "P$48") (pinfunction "PB3_P$48") (pintype "bidirectional"))
    )
    (net (code "9") (name "INT1-MAG3110") (class "Default")
      (node (ref "U1") (pin "P$9") (pinfunction "INT1_P$9") (pintype "bidirectional"))
      (node (ref "U11") (pin "P$1") (pinfunction "PB6_P$1") (pintype "bidirectional"))
    )
    (net (code "10") (name "INT1-MPL311") (class "Default")
      (node (ref "U11") (pin "P$5") (pinfunction "PF4_P$5") (pintype "bidirectional"))
      (node (ref "U5") (pin "P$6") (pinfunction "INT1_P$6") (pintype "bidirectional"))
    )
    (net (code "11") (name "INT2-ADXL362") (class "Default")
      (node (ref "U10") (pin "P$9") (pinfunction "INT2_P$9") (pintype "bidirectional"))
      (node (ref "U11") (pin "P$4") (pinfunction "PB7_P$4") (pintype "bidirectional"))
    )
    (net (code "12") (name "INT2-H3LIS331") (class "Default")
      (node (ref "U11") (pin "P$9") (pinfunction "PE0_P$9") (pintype "bidirectional"))
      (node (ref "U2") (pin "P$9") (pinfunction "INT2_P$9") (pintype "bidirectional"))
    )
    (net (code "13") (name "INT2-L3GD") (class "Default")
      (node (ref "U11") (pin "P$15") (pinfunction "PC5_P$15") (pintype "bidirectional"))
      (node (ref "U3") (pin "P$6") (pinfunction "INT2_P$6") (pintype "bidirectional"))
    )
    (net (code "14") (name "INT2-LIS3DH") (class "Default")
      (node (ref "U11") (pin "P$14") (pinfunction "PC6_P$14") (pintype "bidirectional"))
      (node (ref "U9") (pin "P$9") (pinfunction "INT2_P$9") (pintype "bidirectional"))
    )
    (net (code "15") (name "INT2-LPS331") (class "Default")
      (node (ref "U11") (pin "P$16") (pinfunction "PC4_P$16") (pintype "bidirectional"))
      (node (ref "U4") (pin "P$9") (pinfunction "INT2_P$9") (pintype "bidirectional"))
    )
    (net (code "16") (name "INT2-LSM303") (class "Default")
      (node (ref "U11") (pin "P$10") (pinfunction "PD7_P$10") (pintype "bidirectional"))
      (node (ref "U6") (pin "P$9") (pinfunction "INT2_P$9") (pintype "bidirectional"))
    )
    (net (code "17") (name "INT2-MAX21000") (class "Default")
      (node (ref "U11") (pin "P$13") (pinfunction "PC7_P$13") (pintype "bidirectional"))
      (node (ref "U19") (pin "P$9") (pinfunction "INT2_P$9") (pintype "bidirectional"))
    )
    (net (code "18") (name "LSM9D-DEN-G") (class "Default")
      (node (ref "U17") (pin "P$10") (pinfunction "DEN_G_P$10") (pintype "bidirectional"))
    )
    (net (code "19") (name "LSM9D-DRGY-G") (class "Default")
      (node (ref "U11") (pin "P$8") (pinfunction "PE1_P$8") (pintype "bidirectional"))
      (node (ref "U17") (pin "P$12") (pinfunction "DRDY_G_P$12") (pintype "bidirectional"))
    )
    (net (code "20") (name "LSM9D-INT1-XM") (class "Default")
      (node (ref "U11") (pin "P$7") (pinfunction "PE2_P$7") (pintype "bidirectional"))
      (node (ref "U17") (pin "P$13") (pinfunction "INT1_XM_P$13") (pintype "bidirectional"))
    )
    (net (code "21") (name "LSM9D-INT2-XM") (class "Default")
      (node (ref "U11") (pin "P$6") (pinfunction "PE3_P$6") (pintype "bidirectional"))
      (node (ref "U17") (pin "P$14") (pinfunction "INT2_XM_P$14") (pintype "bidirectional"))
    )
    (net (code "22") (name "MISO-A") (class "Default")
      (node (ref "U11") (pin "P$28") (pinfunction "PF0_P$28") (pintype "bidirectional"))
      (node (ref "U14") (pin "P$9") (pinfunction "A8_P$9") (pintype "bidirectional"))
    )
    (net (code "23") (name "MISO-B") (class "Default")
      (node (ref "R6") (pin "1") (pinfunction "1_1") (pintype "passive"))
      (node (ref "U10") (pin "P$7") (pinfunction "MISO_P$7") (pintype "bidirectional"))
      (node (ref "U14") (pin "P$12") (pinfunction "B8_P$12") (pintype "bidirectional"))
      (node (ref "U15") (pin "P$6") (pinfunction "DOUT_P$6") (pintype "bidirectional"))
      (node (ref "U17") (pin "P$22") (pinfunction "SDO_G_P$22") (pintype "bidirectional"))
      (node (ref "U17") (pin "P$23") (pinfunction "SDO_XM_P$23") (pintype "bidirectional"))
      (node (ref "U19") (pin "P$7") (pinfunction "MISO_P$7") (pintype "bidirectional"))
      (node (ref "U2") (pin "P$7") (pinfunction "MISO_P$7") (pintype "bidirectional"))
      (node (ref "U3") (pin "P$4") (pinfunction "MISO_P$4") (pintype "bidirectional"))
      (node (ref "U4") (pin "P$7") (pinfunction "MISO_P$7") (pintype "bidirectional"))
      (node (ref "U6") (pin "P$7") (pinfunction "MISO_P$7") (pintype "bidirectional"))
      (node (ref "U9") (pin "P$7") (pinfunction "MISO_P$7") (pintype "bidirectional"))
    )
    (net (code "24") (name "MOSI-A") (class "Default")
      (node (ref "U11") (pin "P$29") (pinfunction "PF1_P$29") (pintype "bidirectional"))
      (node (ref "U14") (pin "P$8") (pinfunction "A7_P$8") (pintype "bidirectional"))
    )
    (net (code "25") (name "MOSI-B") (class "Default")
      (node (ref "R4") (pin "1") (pinfunction "1_1") (pintype "passive"))
      (node (ref "U10") (pin "P$6") (pinfunction "MOSI_P$6") (pintype "bidirectional"))
      (node (ref "U14") (pin "P$13") (pinfunction "B7_P$13") (pintype "bidirectional"))
      (node (ref "U15") (pin "P$2") (pinfunction "DIN_P$2") (pintype "bidirectional"))
      (node (ref "U17") (pin "P$24") (pinfunction "SDA_P$24") (pintype "bidirectional"))
      (node (ref "U19") (pin "P$6") (pinfunction "MOSI_P$6") (pintype "bidirectional"))
      (node (ref "U2") (pin "P$6") (pinfunction "MOSI_P$6") (pintype "bidirectional"))
      (node (ref "U3") (pin "P$3") (pinfunction "MOSI_P$3") (pintype "bidirectional"))
      (node (ref "U4") (pin "P$6") (pinfunction "MOSI_P$6") (pintype "bidirectional"))
      (node (ref "U6") (pin "P$6") (pinfunction "MOSI_P$6") (pintype "bidirectional"))
      (node (ref "U9") (pin "P$6") (pinfunction "MOSI_P$6") (pintype "bidirectional"))
    )
    (net (code "26") (name "Net-(C24-Pad2)") (class "Default")
      (node (ref "C24") (pin "2") (pinfunction "2_2") (pintype "passive"))
      (node (ref "R10") (pin "1") (pinfunction "1_1") (pintype "passive"))
    )
    (net (code "27") (name "Net-(IC1A-IN)") (class "Default")
      (node (ref "IC1") (pin "1") (pinfunction "IN_1") (pintype "input"))
      (node (ref "IC2") (pin "1") (pinfunction "IN_1") (pintype "input"))
      (node (ref "IC4") (pin "1") (pinfunction "IN_1") (pintype "input"))
      (node (ref "S1") (pin "1") (pinfunction "O_1") (pintype "passive"))
    )
    (net (code "28") (name "Net-(J1-2)") (class "Default")
      (node (ref "J1") (pin "P$2") (pinfunction "2_P$2") (pintype "bidirectional"))
      (node (ref "S1") (pin "2") (pinfunction "P_2") (pintype "passive"))
    )
    (net (code "29") (name "Net-(LED1-PadA)") (class "Default")
      (node (ref "LED1") (pin "A") (pinfunction "A_A") (pintype "passive"))
      (node (ref "R7") (pin "1") (pinfunction "1_1") (pintype "passive"))
    )
    (net (code "30") (name "Net-(LED2-PadC)") (class "Default")
      (node (ref "LED2") (pin "C") (pinfunction "C_C") (pintype "passive"))
      (node (ref "R12") (pin "2") (pinfunction "2_2") (pintype "passive"))
    )
    (net (code "31") (name "Net-(LED3-PadC)") (class "Default")
      (node (ref "LED3") (pin "C") (pinfunction "C_C") (pintype "passive"))
      (node (ref "R13") (pin "2") (pinfunction "2_2") (pintype "passive"))
    )
    (net (code "32") (name "Net-(LED4-PadC)") (class "Default")
      (node (ref "LED4") (pin "C") (pinfunction "C_C") (pintype "passive"))
      (node (ref "R14") (pin "2") (pinfunction "2_2") (pintype "passive"))
    )
    (net (code "33") (name "Net-(LED5-PadC)") (class "Default")
      (node (ref "LED5") (pin "C") (pinfunction "C_C") (pintype "passive"))
      (node (ref "R15") (pin "2") (pinfunction "2_2") (pintype "passive"))
    )
    (net (code "34") (name "Net-(R3-Pad2)") (class "Default")
      (node (ref "R3") (pin "2") (pinfunction "2_2") (pintype "passive"))
      (node (ref "TP1") (pin "P$1") (pinfunction "P$1_P$1") (pintype "bidirectional"))
    )
    (net (code "35") (name "Net-(R4-Pad2)") (class "Default")
      (node (ref "R4") (pin "2") (pinfunction "2_2") (pintype "passive"))
      (node (ref "TP2") (pin "P$1") (pinfunction "P$1_P$1") (pintype "bidirectional"))
    )
    (net (code "36") (name "Net-(R5-Pad2)") (class "Default")
      (node (ref "R5") (pin "2") (pinfunction "2_2") (pintype "passive"))
      (node (ref "TP6") (pin "P$1") (pinfunction "P$1_P$1") (pintype "bidirectional"))
    )
    (net (code "37") (name "Net-(R6-Pad2)") (class "Default")
      (node (ref "R6") (pin "2") (pinfunction "2_2") (pintype "passive"))
      (node (ref "TP3") (pin "P$1") (pinfunction "P$1_P$1") (pintype "bidirectional"))
    )
    (net (code "38") (name "Net-(R8-Pad2)") (class "Default")
      (node (ref "R8") (pin "2") (pinfunction "2_2") (pintype "passive"))
      (node (ref "TP5") (pin "P$1") (pinfunction "P$1_P$1") (pintype "bidirectional"))
    )
    (net (code "39") (name "Net-(U$13-A)") (class "Default")
      (node (ref "C43") (pin "1") (pinfunction "1_1") (pintype "passive"))
      (node (ref "R16") (pin "2") (pinfunction "2_2") (pintype "passive"))
      (node (ref "U$13") (pin "P$1") (pinfunction "A_P$1") (pintype "bidirectional"))
    )
    (net (code "40") (name "Net-(U$13-B)") (class "Default")
      (node (ref "C44") (pin "1") (pinfunction "1_1") (pintype "passive"))
      (node (ref "U$13") (pin "P$3") (pinfunction "B_P$3") (pintype "bidirectional"))
      (node (ref "U11") (pin "P$40") (pinfunction "OSC0_P$40") (pintype "bidirectional"))
    )
    (net (code "41") (name "Net-(U1-CAP-A)") (class "Default")
      (node (ref "C1") (pin "1") (pinfunction "1_1") (pintype "passive"))
      (node (ref "U1") (pin "P$1") (pinfunction "CAP-A_P$1") (pintype "bidirectional"))
    )
    (net (code "42") (name "Net-(U1-CAP-R)") (class "Default")
      (node (ref "C4") (pin "1") (pinfunction "1_1") (pintype "passive"))
      (node (ref "U1") (pin "P$4") (pinfunction "CAP-R_P$4") (pintype "bidirectional"))
    )
    (net (code "43") (name "Net-(U3-CAP)") (class "Default")
      (node (ref "C10") (pin "1") (pinfunction "1_1") (pintype "passive"))
      (node (ref "U3") (pin "P$14") (pinfunction "CAP_P$14") (pintype "bidirectional"))
    )
    (net (code "44") (name "Net-(U5-CAP)") (class "Default")
      (node (ref "C17") (pin "1") (pinfunction "1_1") (pintype "passive"))
      (node (ref "U5") (pin "P$2") (pinfunction "CAP_P$2") (pintype "bidirectional"))
    )
    (net (code "45") (name "Net-(U6-C1)") (class "Default")
      (node (ref "C18") (pin "1") (pinfunction "1_1") (pintype "passive"))
      (node (ref "U6") (pin "P$15") (pinfunction "C1_P$15") (pintype "bidirectional"))
    )
    (net (code "46") (name "Net-(U6-SETC)") (class "Default")
      (node (ref "C21") (pin "2") (pinfunction "2_2") (pintype "passive"))
      (node (ref "U6") (pin "P$2") (pinfunction "SETC_P$2") (pintype "bidirectional"))
    )
    (net (code "47") (name "Net-(U6-SETP)") (class "Default")
      (node (ref "C21") (pin "1") (pinfunction "1_1") (pintype "passive"))
      (node (ref "U6") (pin "P$3") (pinfunction "SETP_P$3") (pintype "bidirectional"))
    )
    (net (code "48") (name "Net-(U11-OSC1)") (class "Default")
      (node (ref "R16") (pin "1") (pinfunction "1_1") (pintype "passive"))
      (node (ref "U11") (pin "P$41") (pinfunction "OSC1_P$41") (pintype "bidirectional"))
    )
    (net (code "49") (name "Net-(U11-XOSC1)") (class "Default")
      (node (ref "C42") (pin "2") (pinfunction "2_2") (pintype "passive"))
      (node (ref "U$12") (pin "P$2") (pinfunction "P$2_P$2") (pintype "bidirectional"))
      (node (ref "U11") (pin "P$36") (pinfunction "XOSC1_P$36") (pintype "bidirectional"))
    )
    (net (code "50") (name "Net-(U11-XOSCO)") (class "Default")
      (node (ref "C41") (pin "1") (pinfunction "1_1") (pintype "passive"))
      (node (ref "U$12") (pin "P$1") (pinfunction "P$1_P$1") (pintype "bidirectional"))
      (node (ref "U11") (pin "P$34") (pinfunction "XOSCO_P$34") (pintype "bidirectional"))
    )
    (net (code "51") (name "Net-(U11-~{RST})") (class "Default")
      (node (ref "C30") (pin "2") (pinfunction "2_2") (pintype "passive"))
      (node (ref "R17") (pin "1") (pinfunction "1_1") (pintype "passive"))
      (node (ref "U11") (pin "P$38") (pinfunction "~{RST}_P$38") (pintype "bidirectional"))
    )
    (net (code "52") (name "Net-(U17-C1_XM)") (class "Default")
      (node (ref "C48") (pin "1") (pinfunction "1_1") (pintype "passive"))
      (node (ref "U17") (pin "P$7") (pinfunction "C1_XM_P$7") (pintype "bidirectional"))
    )
    (net (code "53") (name "Net-(U17-SETC_XM)") (class "Default")
      (node (ref "C49") (pin "2") (pinfunction "2_2") (pintype "passive"))
      (node (ref "U17") (pin "P$8") (pinfunction "SETC_XM_P$8") (pintype "bidirectional"))
    )
    (net (code "54") (name "Net-(U17-SETP_XM)") (class "Default")
      (node (ref "C49") (pin "1") (pinfunction "1_1") (pintype "passive"))
      (node (ref "U17") (pin "P$9") (pinfunction "SETP_XM_P$9") (pintype "bidirectional"))
    )
    (net (code "55") (name "SCL-0") (class "Default")
      (node (ref "R1") (pin "1") (pinfunction "1_1") (pintype "passive"))
      (node (ref "R5") (pin "1") (pinfunction "1_1") (pintype "passive"))
      (node (ref "U1") (pin "P$7") (pinfunction "SCL_P$7") (pintype "bidirectional"))
      (node (ref "U11") (pin "P$23") (pinfunction "PA6_P$23") (pintype "bidirectional"))
      (node (ref "U22") (pin "P$10") (pinfunction "SCL_P$10") (pintype "bidirectional"))
      (node (ref "U5") (pin "P$8") (pinfunction "SCL_P$8") (pintype "bidirectional"))
    )
    (net (code "56") (name "SCLK-A") (class "Default")
      (node (ref "U11") (pin "P$30") (pinfunction "PF2_P$30") (pintype "bidirectional"))
      (node (ref "U14") (pin "P$7") (pinfunction "A6_P$7") (pintype "bidirectional"))
    )
    (net (code "57") (name "SCLK-B") (class "Default")
      (node (ref "R3") (pin "1") (pinfunction "1_1") (pintype "passive"))
      (node (ref "U10") (pin "P$4") (pinfunction "SCLK_P$4") (pintype "bidirectional"))
      (node (ref "U14") (pin "P$14") (pinfunction "B6_P$14") (pintype "bidirectional"))
      (node (ref "U15") (pin "P$4") (pinfunction "SCLK_P$4") (pintype "bidirectional"))
      (node (ref "U17") (pin "P$21") (pinfunction "SCL_P$21") (pintype "bidirectional"))
      (node (ref "U19") (pin "P$4") (pinfunction "SCLK_P$4") (pintype "bidirectional"))
      (node (ref "U2") (pin "P$4") (pinfunction "SCLK_P$4") (pintype "bidirectional"))
      (node (ref "U3") (pin "P$2") (pinfunction "SCL_P$2") (pintype "bidirectional"))
      (node (ref "U4") (pin "P$4") (pinfunction "SCL_P$4") (pintype "bidirectional"))
      (node (ref "U6") (pin "P$4") (pinfunction "SCL_P$4") (pintype "bidirectional"))
      (node (ref "U9") (pin "P$4") (pinfunction "SCL_P$4") (pintype "bidirectional"))
    )
    (net (code "58") (name "SD-CARD-INSERT") (class "Default")
      (node (ref "J3") (pin "P$8") (pinfunction "SWITCH2_P$8") (pintype "bidirectional"))
      (node (ref "U11") (pin "P$60") (pinfunction "PE5_P$60") (pintype "bidirectional"))
    )
    (net (code "59") (name "SD-CS") (class "Default")
      (node (ref "J3") (pin "P$2") (pinfunction "~{CS}_P$2") (pintype "bidirectional"))
      (node (ref "U11") (pin "P$62") (pinfunction "PD1_P$62") (pintype "bidirectional"))
    )
    (net (code "60") (name "SD-MISO") (class "Default")
      (node (ref "J3") (pin "P$7") (pinfunction "D0_P$7") (pintype "bidirectional"))
      (node (ref "U11") (pin "P$63") (pinfunction "PD2_P$63") (pintype "bidirectional"))
    )
    (net (code "61") (name "SD-MOSI") (class "Default")
      (node (ref "J3") (pin "P$3") (pinfunction "DI_P$3") (pintype "bidirectional"))
      (node (ref "U11") (pin "P$64") (pinfunction "PD3_P$64") (pintype "bidirectional"))
    )
    (net (code "62") (name "SD-SCLK") (class "Default")
      (node (ref "J3") (pin "P$5") (pinfunction "SCLK_P$5") (pintype "bidirectional"))
      (node (ref "U11") (pin "P$61") (pinfunction "PD0_P$61") (pintype "bidirectional"))
    )
    (net (code "63") (name "SDA-0") (class "Default")
      (node (ref "R2") (pin "1") (pinfunction "1_1") (pintype "passive"))
      (node (ref "R8") (pin "1") (pinfunction "1_1") (pintype "passive"))
      (node (ref "U1") (pin "P$6") (pinfunction "SDA_P$6") (pintype "bidirectional"))
      (node (ref "U11") (pin "P$24") (pinfunction "PA7_P$24") (pintype "bidirectional"))
      (node (ref "U22") (pin "P$1") (pinfunction "SDA_P$1") (pintype "bidirectional"))
      (node (ref "U5") (pin "P$7") (pinfunction "SDA_P$7") (pintype "bidirectional"))
    )
    (net (code "64") (name "SPI-ADDR0") (class "Default")
      (node (ref "U11") (pin "P$17") (pinfunction "PA0_P$17") (pintype "bidirectional"))
      (node (ref "U21") (pin "P$15") (pinfunction "A_P$15") (pintype "bidirectional"))
    )
    (net (code "65") (name "SPI-ADDR1") (class "Default")
      (node (ref "U11") (pin "P$18") (pinfunction "PA1_P$18") (pintype "bidirectional"))
      (node (ref "U21") (pin "P$14") (pinfunction "B_P$14") (pintype "bidirectional"))
    )
    (net (code "66") (name "SPI-ADDR2") (class "Default")
      (node (ref "U11") (pin "P$19") (pinfunction "PA2_P$19") (pintype "bidirectional"))
      (node (ref "U21") (pin "P$13") (pinfunction "C_P$13") (pintype "bidirectional"))
    )
    (net (code "67") (name "SPI-ADDR3") (class "Default")
      (node (ref "U11") (pin "P$20") (pinfunction "PA3_P$20") (pintype "bidirectional"))
      (node (ref "U21") (pin "P$12") (pinfunction "D_P$12") (pintype "bidirectional"))
    )
    (net (code "68") (name "SPI-ENABLE") (class "Default")
      (node (ref "U11") (pin "P$31") (pinfunction "PF3_P$31") (pintype "bidirectional"))
      (node (ref "U14") (pin "P$10") (pinfunction "OE_P$10") (pintype "bidirectional"))
    )
    (net (code "69") (name "SWCLK") (class "Default")
      (node (ref "U11") (pin "P$52") (pinfunction "PC0_P$52") (pintype "bidirectional"))
      (node (ref "U7") (pin "P$1") (pinfunction "1_P$1") (pintype "bidirectional"))
    )
    (net (code "70") (name "SWDIO") (class "Default")
      (node (ref "U11") (pin "P$51") (pinfunction "PC1_P$51") (pintype "bidirectional"))
      (node (ref "U7") (pin "P$2") (pinfunction "2_P$2") (pintype "bidirectional"))
    )
    (net (code "71") (name "SWO") (class "Default")
      (node (ref "U11") (pin "P$49") (pinfunction "PC3_P$49") (pintype "bidirectional"))
      (node (ref "U7") (pin "P$4") (pinfunction "4_P$4") (pintype "bidirectional"))
    )
    (net (code "72") (name "TDI") (class "Default")
      (node (ref "U11") (pin "P$50") (pinfunction "PC2_P$50") (pintype "bidirectional"))
      (node (ref "U7") (pin "P$3") (pinfunction "3_P$3") (pintype "bidirectional"))
    )
    (net (code "73") (name "U6RX") (class "Default")
      (node (ref "J2") (pin "P$1") (pinfunction "1_P$1") (pintype "bidirectional"))
      (node (ref "TP8") (pin "P$1") (pinfunction "P$1_P$1") (pintype "bidirectional"))
      (node (ref "U11") (pin "P$43") (pinfunction "PD4_P$43") (pintype "bidirectional"))
    )
    (net (code "74") (name "U6TX") (class "Default")
      (node (ref "J2") (pin "P$2") (pinfunction "2_P$2") (pintype "bidirectional"))
      (node (ref "TP7") (pin "P$1") (pinfunction "P$1_P$1") (pintype "bidirectional"))
      (node (ref "U11") (pin "P$44") (pinfunction "PD5_P$44") (pintype "bidirectional"))
    )
    (net (code "75") (name "unconnected-(IC1A-OUT-Pad3)") (class "Default")
      (node (ref "IC1") (pin "3") (pinfunction "OUT_3") (pintype "output"))
    )
    (net (code "76") (name "unconnected-(J3-GND#1-PadP$10)") (class "Default")
      (node (ref "J3") (pin "P$10") (pinfunction "GND#1_P$10") (pintype "bidirectional"))
    )
    (net (code "77") (name "unconnected-(J3-GND#2-PadP$11)") (class "Default")
      (node (ref "J3") (pin "P$11") (pinfunction "GND#2_P$11") (pintype "bidirectional"))
    )
    (net (code "78") (name "unconnected-(J3-GND#3-PadP$12)") (class "Default")
      (node (ref "J3") (pin "P$12") (pinfunction "GND#3_P$12") (pintype "bidirectional"))
    )
    (net (code "79") (name "unconnected-(J3-GND#4-PadP$13)") (class "Default")
      (node (ref "J3") (pin "P$13") (pinfunction "GND#4_P$13") (pintype "bidirectional"))
    )
    (net (code "80") (name "unconnected-(J3-RSV-PadP$1)") (class "Default")
      (node (ref "J3") (pin "P$1") (pinfunction "RSV_P$1") (pintype "bidirectional"))
    )
    (net (code "81") (name "unconnected-(S1-S-Pad3)") (class "Default")
      (node (ref "S1") (pin "3") (pinfunction "S_3") (pintype "passive"))
    )
    (net (code "82") (name "unconnected-(U1-NC-PadP$3)") (class "Default")
      (node (ref "U1") (pin "P$3") (pinfunction "NC_P$3") (pintype "bidirectional"))
    )
    (net (code "83") (name "unconnected-(U2-INT1-PadP$11)") (class "Default")
      (node (ref "U2") (pin "P$11") (pinfunction "INT1_P$11") (pintype "bidirectional"))
    )
    (net (code "84") (name "unconnected-(U2-NC#0-PadP$2)") (class "Default")
      (node (ref "U2") (pin "P$2") (pinfunction "NC#0_P$2") (pintype "bidirectional"))
    )
    (net (code "85") (name "unconnected-(U2-NC#1-PadP$3)") (class "Default")
      (node (ref "U2") (pin "P$3") (pinfunction "NC#1_P$3") (pintype "bidirectional"))
    )
    (net (code "86") (name "unconnected-(U3-INT1-PadP$7)") (class "Default")
      (node (ref "U3") (pin "P$7") (pinfunction "INT1_P$7") (pintype "bidirectional"))
    )
    (net (code "87") (name "unconnected-(U4-NC$0-PadP$2)") (class "Default")
      (node (ref "U4") (pin "P$2") (pinfunction "NC$0_P$2") (pintype "bidirectional"))
    )
    (net (code "88") (name "unconnected-(U4-NC$1-PadP$3)") (class "Default")
      (node (ref "U4") (pin "P$3") (pinfunction "NC$1_P$3") (pintype "bidirectional"))
    )
    (net (code "89") (name "unconnected-(U5-INT2-PadP$5)") (class "Default")
      (node (ref "U5") (pin "P$5") (pinfunction "INT2_P$5") (pintype "bidirectional"))
    )
    (net (code "90") (name "unconnected-(U6-INT1-PadP$11)") (class "Default")
      (node (ref "U6") (pin "P$11") (pinfunction "INT1_P$11") (pintype "bidirectional"))
    )
    (net (code "91") (name "unconnected-(U9-ADC1-PadP$16)") (class "Default")
      (node (ref "U9") (pin "P$16") (pinfunction "ADC1_P$16") (pintype "bidirectional"))
    )
    (net (code "92") (name "unconnected-(U9-ADC2-PadP$15)") (class "Default")
      (node (ref "U9") (pin "P$15") (pinfunction "ADC2_P$15") (pintype "bidirectional"))
    )
    (net (code "93") (name "unconnected-(U9-ADC3-PadP$13)") (class "Default")
      (node (ref "U9") (pin "P$13") (pinfunction "ADC3_P$13") (pintype "bidirectional"))
    )
    (net (code "94") (name "unconnected-(U9-INT1-PadP$11)") (class "Default")
      (node (ref "U9") (pin "P$11") (pinfunction "INT1_P$11") (pintype "bidirectional"))
    )
    (net (code "95") (name "unconnected-(U9-NC$0-PadP$2)") (class "Default")
      (node (ref "U9") (pin "P$2") (pinfunction "NC$0_P$2") (pintype "bidirectional"))
    )
    (net (code "96") (name "unconnected-(U9-NC$1-PadP$3)") (class "Default")
      (node (ref "U9") (pin "P$3") (pinfunction "NC$1_P$3") (pintype "bidirectional"))
    )
    (net (code "97") (name "unconnected-(U10-INT1-PadP$11)") (class "Default")
      (node (ref "U10") (pin "P$11") (pinfunction "INT1_P$11") (pintype "bidirectional"))
    )
    (net (code "98") (name "unconnected-(U10-NC$0-PadP$2)") (class "Default")
      (node (ref "U10") (pin "P$2") (pinfunction "NC$0_P$2") (pintype "bidirectional"))
    )
    (net (code "99") (name "unconnected-(U10-NC$1-PadP$15)") (class "Default")
      (node (ref "U10") (pin "P$15") (pinfunction "NC$1_P$15") (pintype "bidirectional"))
    )
    (net (code "100") (name "unconnected-(U10-RSVD$0-PadP$3)") (class "Default")
      (node (ref "U10") (pin "P$3") (pinfunction "RSVD$0_P$3") (pintype "bidirectional"))
    )
    (net (code "101") (name "unconnected-(U10-RSVD$2-PadP$10)") (class "Default")
      (node (ref "U10") (pin "P$10") (pinfunction "RSVD$2_P$10") (pintype "bidirectional"))
    )
    (net (code "102") (name "unconnected-(U11-PA4-PadP$21)") (class "Default")
      (node (ref "U11") (pin "P$21") (pinfunction "PA4_P$21") (pintype "bidirectional"))
    )
    (net (code "103") (name "unconnected-(U11-PA5-PadP$22)") (class "Default")
      (node (ref "U11") (pin "P$22") (pinfunction "PA5_P$22") (pintype "bidirectional"))
    )
    (net (code "104") (name "unconnected-(U11-PB5-PadP$57)") (class "Default")
      (node (ref "U11") (pin "P$57") (pinfunction "PB5_P$57") (pintype "bidirectional"))
    )
    (net (code "105") (name "unconnected-(U11-PD6-PadP$53)") (class "Default")
      (node (ref "U11") (pin "P$53") (pinfunction "PD6_P$53") (pintype "bidirectional"))
    )
    (net (code "106") (name "unconnected-(U11-PE4-PadP$59)") (class "Default")
      (node (ref "U11") (pin "P$59") (pinfunction "PE4_P$59") (pintype "bidirectional"))
    )
    (net (code "107") (name "unconnected-(U11-~{HIB}-PadP$33)") (class "Default")
      (node (ref "U11") (pin "P$33") (pinfunction "~{HIB}_P$33") (pintype "bidirectional"))
    )
    (net (code "108") (name "unconnected-(U17-RES#0-PadP$1)") (class "Default")
      (node (ref "U17") (pin "P$1") (pinfunction "RES#0_P$1") (pintype "bidirectional"))
    )
    (net (code "109") (name "unconnected-(U19-DSYNC-PadP$12)") (class "Default")
      (node (ref "U19") (pin "P$12") (pinfunction "DSYNC_P$12") (pintype "bidirectional"))
    )
    (net (code "110") (name "unconnected-(U19-INT1-PadP$11)") (class "Default")
      (node (ref "U19") (pin "P$11") (pinfunction "INT1_P$11") (pintype "bidirectional"))
    )
    (net (code "111") (name "unconnected-(U19-NC#0-PadP$2)") (class "Default")
      (node (ref "U19") (pin "P$2") (pinfunction "NC#0_P$2") (pintype "bidirectional"))
    )
    (net (code "112") (name "unconnected-(U19-NC#1-PadP$3)") (class "Default")
      (node (ref "U19") (pin "P$3") (pinfunction "NC#1_P$3") (pintype "bidirectional"))
    )
    (net (code "113") (name "unconnected-(U19-NC#2-PadP$16)") (class "Default")
      (node (ref "U19") (pin "P$16") (pinfunction "NC#2_P$16") (pintype "bidirectional"))
    )
    (net (code "114") (name "unconnected-(U19-RSVD#1-PadP$13)") (class "Default")
      (node (ref "U19") (pin "P$13") (pinfunction "RSVD#1_P$13") (pintype "bidirectional"))
    )
    (net (code "115") (name "unconnected-(U22-FLOAT-PadP$11)") (class "Default")
      (node (ref "U22") (pin "P$11") (pinfunction "FLOAT_P$11") (pintype "bidirectional"))
    )
    (net (code "116") (name "unconnected-(U22-VINN-PadP$7)") (class "Default")
      (node (ref "U22") (pin "P$7") (pinfunction "VINN_P$7") (pintype "bidirectional"))
    )
    (net (code "117") (name "unconnected-(U22-VINP-PadP$6)") (class "Default")
      (node (ref "U22") (pin "P$6") (pinfunction "VINP_P$6") (pintype "bidirectional"))
    )
    (net (code "118") (name "~{CS-ADT7301}") (class "Default")
      (node (ref "U15") (pin "P$5") (pinfunction "~{CS}_P$5") (pintype "bidirectional"))
      (node (ref "U21") (pin "P$11") (pinfunction "9_P$11") (pintype "bidirectional"))
    )
    (net (code "119") (name "~{CS-ADXL362}") (class "Default")
      (node (ref "U10") (pin "P$8") (pinfunction "~{CS}_P$8") (pintype "bidirectional"))
      (node (ref "U21") (pin "P$1") (pinfunction "0_P$1") (pintype "bidirectional"))
    )
    (net (code "120") (name "~{CS-H3LIS331DLTR}") (class "Default")
      (node (ref "U2") (pin "P$8") (pinfunction "~{CS}_P$8") (pintype "bidirectional"))
      (node (ref "U21") (pin "P$2") (pinfunction "1_P$2") (pintype "bidirectional"))
    )
    (net (code "121") (name "~{CS-LIS3DH}") (class "Default")
      (node (ref "U21") (pin "P$7") (pinfunction "6_P$7") (pintype "bidirectional"))
      (node (ref "U9") (pin "P$8") (pinfunction "~{CS}_P$8") (pintype "bidirectional"))
    )
    (net (code "122") (name "~{CS-LPS331}") (class "Default")
      (node (ref "U21") (pin "P$10") (pinfunction "8_P$10") (pintype "bidirectional"))
      (node (ref "U4") (pin "P$8") (pinfunction "~{CS}_P$8") (pintype "bidirectional"))
    )
    (net (code "123") (name "~{CS-LS3GD20}") (class "Default")
      (node (ref "U21") (pin "P$9") (pinfunction "7_P$9") (pintype "bidirectional"))
      (node (ref "U3") (pin "P$5") (pinfunction "~{CS}_P$5") (pintype "bidirectional"))
    )
    (net (code "124") (name "~{CS-LSM9D30-G}") (class "Default")
      (node (ref "U17") (pin "P$19") (pinfunction "~{CS_G}_P$19") (pintype "bidirectional"))
      (node (ref "U21") (pin "P$3") (pinfunction "2_P$3") (pintype "bidirectional"))
    )
    (net (code "125") (name "~{CS-LSM9DS0-XM}") (class "Default")
      (node (ref "U17") (pin "P$20") (pinfunction "~{CS_XM}_P$20") (pintype "bidirectional"))
      (node (ref "U21") (pin "P$4") (pinfunction "3_P$4") (pintype "bidirectional"))
    )
    (net (code "126") (name "~{CS-LSM303}") (class "Default")
      (node (ref "U21") (pin "P$6") (pinfunction "5_P$6") (pintype "bidirectional"))
      (node (ref "U6") (pin "P$8") (pinfunction "~{CS}_P$8") (pintype "bidirectional"))
    )
    (net (code "127") (name "~{CS-MAX21000}") (class "Default")
      (node (ref "U19") (pin "P$8") (pinfunction "~{CS}_P$8") (pintype "bidirectional"))
      (node (ref "U21") (pin "P$5") (pinfunction "4_P$5") (pintype "bidirectional"))
    )
  )
)
